# FLIR.net
KiCad netlist of a schematic drawn in Altium Designer
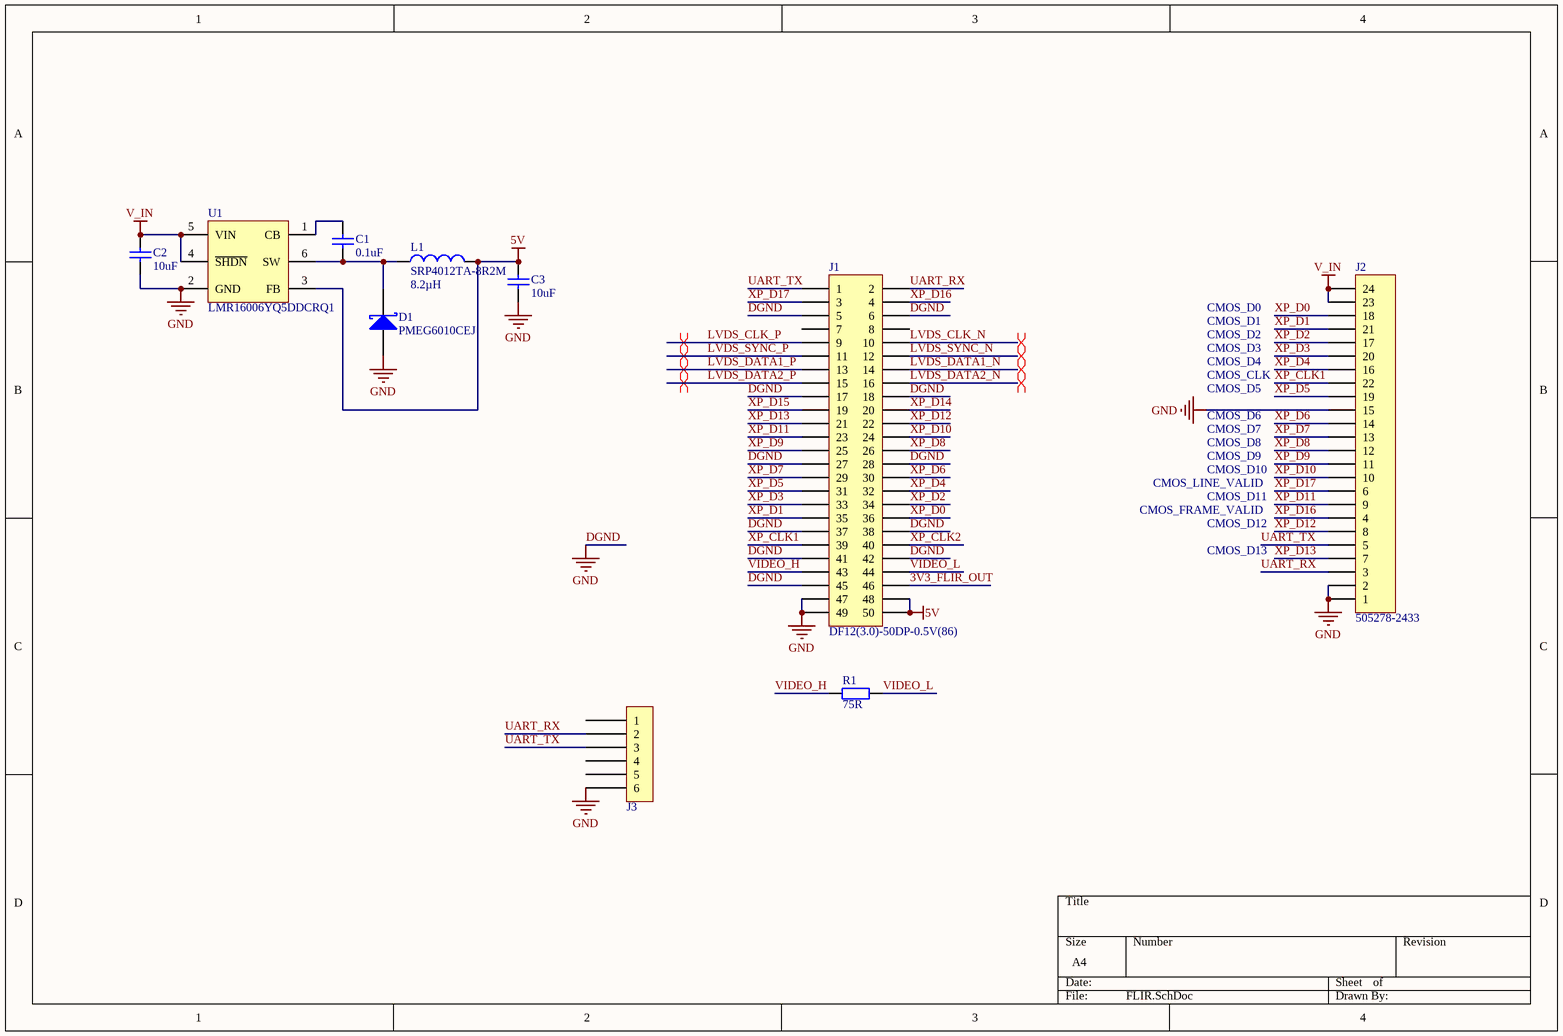
[diagram p0: FLIR.SchDoc]

(export (version "E")
  (design (tool "Eeschema 10.0.6"))
  (components
    (comp (ref "C1")
      (value "0.1uF")
      (footprint "0603C_L")
      (description "CAP CER 0603 0.1uF 16V X7R 5%")
      (fields
        (field (name "MANUFACTURER") "Vishay / Vitramon")
        (field (name "MANUFACTURER PART NUMBER") "VJ0603Y104JXJPW1BC")
      )
      (libsource (lib "KMTI-main") (part "VJ0603Y104JXJPW1BC"))
    )
    (comp (ref "C2")
      (value "10uF")
      (footprint "1206_1.6_L")
      (description "CAP CER 1206 10uF 50V X5R 20%")
      (fields
        (field (name "MANUFACTURER") "Murata Electronics")
        (field (name "MANUFACTURER PART NUMBER") "GRM31CR61H106MA12L")
      )
      (libsource (lib "KMTI-main") (part "GRM31CR61H106MA12L"))
    )
    (comp (ref "C3")
      (value "10uF")
      (footprint "1206_1.6_L")
      (description "CAP CER 1206 10uF 25V X7R 10%")
      (fields
        (field (name "MANUFACTURER") "Taiyo Yuden")
        (field (name "MANUFACTURER PART NUMBER") "TMK316B7106KL-TD")
      )
      (libsource (lib "KMTI-main") (part "TMK316B7106KL-TD"))
    )
    (comp (ref "D1")
      (value "PMEG6010CEJ")
      (footprint "SOD323M")
      (description "DIODE SCHOTTKY 60V 1A SOD323F")
      (fields
        (field (name "MANUFACTURER") "NXP USA Inc.")
        (field (name "MANUFACTURER PART NUMBER") "PMEG6010CEJ,115")
      )
      (libsource (lib "KMTI-main") (part "PMEG6010CEJ,115"))
    )
    (comp (ref "J1")
      (value "DF12(3.0)-50DP-0.5V(86)")
      (footprint "DF12(3.0)-50DP-0.5V(86)")
      (description "Board to Board & Mezzanine Connectors 50P V SMT DR HDR 3.0MM STACK HT GOLD")
      (fields (field (name "MANUFACTURER") "Hirose Connector"))
      (libsource (lib "KMTI-main") (part "DF12(3.0)-50DP-0.5V(86)"))
    )
    (comp (ref "J2")
      (value "505278-2433")
      (footprint "505278-2433")
      (description "0.5 FFC ZIF BTM CONT EMBT PKG 24")
      (fields
        (field (name "MANUFACTURER") "Molex, LLC")
        (field (name "MANUFACTURER PART NUMBER") "5052782433")
      )
      (libsource (lib "KMTI-main") (part "5052782433"))
    )
    (comp (ref "J3")
      (value "BM06B-GHS-TBT(LF)(SN)(N)")
      (footprint "BM06B-GHS-TBT")
      (description "CONN HEADER GH TOP 6POS 1.25MM")
      (fields (field (name "MANUFACTURER") "JST Sales America Inc."))
      (libsource (lib "KMTI-main") (part "BM06B-GHS-TBT(LF)(SN)(N)"))
    )
    (comp (ref "L1")
      (value "SRP4012TA-8R2M")
      (footprint "INDP4541X12M")
      (description "FIXED IND 8.2UH 1.4A 376 MOHM")
      (fields
        (field (name "MANUFACTURER") "Bourns Inc.")
        (field (name "TOLERANCE") "±20%")
        (field (name "INDUCTANCE") "8.2µH")
      )
      (libsource (lib "KMTI-main") (part "SRP4012TA-8R2M"))
    )
    (comp (ref "R1")
      (value "75R")
      (footprint "0603R_0.45_H")
      (description "RES SMD 75 OHM 1% 1/10W 0603")
      (fields
        (field (name "MANUFACTURER") "Vishay Dale")
        (field (name "MANUFACTURER PART NUMBER") "CRCW060375R0FKEA")
      )
      (libsource (lib "KMTI-main") (part "CRCW060375R0FKEA"))
    )
    (comp (ref "U1")
      (value "LMR16006YQ5DDCRQ1")
      (footprint "SOT95P280X110-6M")
      (description "IC REG BUCK 5V 0.6A 6SOT")
      (fields (field (name "MANUFACTURER") "Texas Instruments"))
      (libsource (lib "Power") (part "LMR16006YQ5DDCRQ1"))
    )
  )
  (nets
    (net (code "1") (name "/3V3_FLIR_OUT") (class "Default")
      (node (ref "J1") (pin "46") (pinfunction "46_46") (pintype "passive"))
    )
    (net (code "2") (name "/LVDS_CLK_N") (class "Default")
      (node (ref "J1") (pin "10") (pinfunction "10_10") (pintype "passive"))
    )
    (net (code "3") (name "/LVDS_CLK_P") (class "Default")
      (node (ref "J1") (pin "9") (pinfunction "9_9") (pintype "passive"))
    )
    (net (code "4") (name "/LVDS_DATA1_N") (class "Default")
      (node (ref "J1") (pin "14") (pinfunction "14_14") (pintype "passive"))
    )
    (net (code "5") (name "/LVDS_DATA1_P") (class "Default")
      (node (ref "J1") (pin "13") (pinfunction "13_13") (pintype "passive"))
    )
    (net (code "6") (name "/LVDS_DATA2_N") (class "Default")
      (node (ref "J1") (pin "16") (pinfunction "16_16") (pintype "passive"))
    )
    (net (code "7") (name "/LVDS_DATA2_P") (class "Default")
      (node (ref "J1") (pin "15") (pinfunction "15_15") (pintype "passive"))
    )
    (net (code "8") (name "/LVDS_SYNC_N") (class "Default")
      (node (ref "J1") (pin "12") (pinfunction "12_12") (pintype "passive"))
    )
    (net (code "9") (name "/LVDS_SYNC_P") (class "Default")
      (node (ref "J1") (pin "11") (pinfunction "11_11") (pintype "passive"))
    )
    (net (code "10") (name "/UART_RX") (class "Default")
      (node (ref "J1") (pin "2") (pinfunction "2_2") (pintype "passive"))
      (node (ref "J2") (pin "3") (pinfunction "3_3") (pintype "passive"))
      (node (ref "J3") (pin "2") (pinfunction "2_2") (pintype "passive"))
    )
    (net (code "11") (name "/UART_TX") (class "Default")
      (node (ref "J1") (pin "1") (pinfunction "1_1") (pintype "passive"))
      (node (ref "J2") (pin "5") (pinfunction "5_5") (pintype "passive"))
      (node (ref "J3") (pin "3") (pinfunction "3_3") (pintype "passive"))
    )
    (net (code "12") (name "/VIDEO_H") (class "Default")
      (node (ref "J1") (pin "43") (pinfunction "43_43") (pintype "passive"))
      (node (ref "R1") (pin "1") (pinfunction "1_1") (pintype "passive"))
    )
    (net (code "13") (name "/VIDEO_L") (class "Default")
      (node (ref "J1") (pin "44") (pinfunction "44_44") (pintype "passive"))
      (node (ref "R1") (pin "2") (pinfunction "2_2") (pintype "passive"))
    )
    (net (code "14") (name "/XP_CLK1") (class "Default")
      (node (ref "J1") (pin "39") (pinfunction "39_39") (pintype "passive"))
      (node (ref "J2") (pin "22") (pinfunction "22_22") (pintype "passive"))
    )
    (net (code "15") (name "/XP_CLK2") (class "Default")
      (node (ref "J1") (pin "40") (pinfunction "40_40") (pintype "passive"))
    )
    (net (code "16") (name "/XP_D0") (class "Default")
      (node (ref "J1") (pin "36") (pinfunction "36_36") (pintype "passive"))
      (node (ref "J2") (pin "18") (pinfunction "18_18") (pintype "passive"))
    )
    (net (code "17") (name "/XP_D1") (class "Default")
      (node (ref "J1") (pin "35") (pinfunction "35_35") (pintype "passive"))
      (node (ref "J2") (pin "21") (pinfunction "21_21") (pintype "passive"))
    )
    (net (code "18") (name "/XP_D2") (class "Default")
      (node (ref "J1") (pin "34") (pinfunction "34_34") (pintype "passive"))
      (node (ref "J2") (pin "17") (pinfunction "17_17") (pintype "passive"))
    )
    (net (code "19") (name "/XP_D3") (class "Default")
      (node (ref "J1") (pin "33") (pinfunction "33_33") (pintype "passive"))
      (node (ref "J2") (pin "20") (pinfunction "20_20") (pintype "passive"))
    )
    (net (code "20") (name "/XP_D4") (class "Default")
      (node (ref "J1") (pin "32") (pinfunction "32_32") (pintype "passive"))
      (node (ref "J2") (pin "16") (pinfunction "16_16") (pintype "passive"))
    )
    (net (code "21") (name "/XP_D5") (class "Default")
      (node (ref "J1") (pin "31") (pinfunction "31_31") (pintype "passive"))
      (node (ref "J2") (pin "19") (pinfunction "19_19") (pintype "passive"))
    )
    (net (code "22") (name "/XP_D6") (class "Default")
      (node (ref "J1") (pin "30") (pinfunction "30_30") (pintype "passive"))
      (node (ref "J2") (pin "14") (pinfunction "14_14") (pintype "passive"))
    )
    (net (code "23") (name "/XP_D7") (class "Default")
      (node (ref "J1") (pin "29") (pinfunction "29_29") (pintype "passive"))
      (node (ref "J2") (pin "13") (pinfunction "13_13") (pintype "passive"))
    )
    (net (code "24") (name "/XP_D8") (class "Default")
      (node (ref "J1") (pin "26") (pinfunction "26_26") (pintype "passive"))
      (node (ref "J2") (pin "12") (pinfunction "12_12") (pintype "passive"))
    )
    (net (code "25") (name "/XP_D9") (class "Default")
      (node (ref "J1") (pin "25") (pinfunction "25_25") (pintype "passive"))
      (node (ref "J2") (pin "11") (pinfunction "11_11") (pintype "passive"))
    )
    (net (code "26") (name "/XP_D10") (class "Default")
      (node (ref "J1") (pin "24") (pinfunction "24_24") (pintype "passive"))
      (node (ref "J2") (pin "10") (pinfunction "10_10") (pintype "passive"))
    )
    (net (code "27") (name "/XP_D11") (class "Default")
      (node (ref "J1") (pin "23") (pinfunction "23_23") (pintype "passive"))
      (node (ref "J2") (pin "9") (pinfunction "9_9") (pintype "passive"))
    )
    (net (code "28") (name "/XP_D12") (class "Default")
      (node (ref "J1") (pin "22") (pinfunction "22_22") (pintype "passive"))
      (node (ref "J2") (pin "8") (pinfunction "8_8") (pintype "passive"))
    )
    (net (code "29") (name "/XP_D13") (class "Default")
      (node (ref "J1") (pin "21") (pinfunction "21_21") (pintype "passive"))
      (node (ref "J2") (pin "7") (pinfunction "7_7") (pintype "passive"))
    )
    (net (code "30") (name "/XP_D14") (class "Default")
      (node (ref "J1") (pin "20") (pinfunction "20_20") (pintype "passive"))
    )
    (net (code "31") (name "/XP_D15") (class "Default")
      (node (ref "J1") (pin "19") (pinfunction "19_19") (pintype "passive"))
    )
    (net (code "32") (name "/XP_D16") (class "Default")
      (node (ref "J1") (pin "4") (pinfunction "4_4") (pintype "passive"))
      (node (ref "J2") (pin "4") (pinfunction "4_4") (pintype "passive"))
    )
    (net (code "33") (name "/XP_D17") (class "Default")
      (node (ref "J1") (pin "3") (pinfunction "3_3") (pintype "passive"))
      (node (ref "J2") (pin "6") (pinfunction "6_6") (pintype "passive"))
    )
    (net (code "34") (name "5V") (class "Default")
      (node (ref "C3") (pin "2") (pinfunction "2_2") (pintype "passive"))
      (node (ref "J1") (pin "48") (pinfunction "48_48") (pintype "passive"))
      (node (ref "J1") (pin "50") (pinfunction "50_50") (pintype "passive"))
      (node (ref "L1") (pin "2") (pinfunction "2_2") (pintype "passive"))
      (node (ref "U1") (pin "3") (pinfunction "FB_3") (pintype "passive"))
    )
    (net (code "35") (name "GND") (class "Default")
      (node (ref "C2") (pin "1") (pinfunction "1_1") (pintype "passive"))
      (node (ref "C3") (pin "1") (pinfunction "1_1") (pintype "passive"))
      (node (ref "D1") (pin "2") (pinfunction "A_2") (pintype "passive"))
      (node (ref "J1") (pin "17") (pinfunction "17_17") (pintype "passive"))
      (node (ref "J1") (pin "18") (pinfunction "18_18") (pintype "passive"))
      (node (ref "J1") (pin "27") (pinfunction "27_27") (pintype "passive"))
      (node (ref "J1") (pin "28") (pinfunction "28_28") (pintype "passive"))
      (node (ref "J1") (pin "37") (pinfunction "37_37") (pintype "passive"))
      (node (ref "J1") (pin "38") (pinfunction "38_38") (pintype "passive"))
      (node (ref "J1") (pin "41") (pinfunction "41_41") (pintype "passive"))
      (node (ref "J1") (pin "42") (pinfunction "42_42") (pintype "passive"))
      (node (ref "J1") (pin "45") (pinfunction "45_45") (pintype "passive"))
      (node (ref "J1") (pin "47") (pinfunction "47_47") (pintype "passive"))
      (node (ref "J1") (pin "49") (pinfunction "49_49") (pintype "passive"))
      (node (ref "J1") (pin "5") (pinfunction "5_5") (pintype "passive"))
      (node (ref "J1") (pin "6") (pinfunction "6_6") (pintype "passive"))
      (node (ref "J2") (pin "1") (pinfunction "1_1") (pintype "passive"))
      (node (ref "J2") (pin "15") (pinfunction "15_15") (pintype "passive"))
      (node (ref "J2") (pin "2") (pinfunction "2_2") (pintype "passive"))
      (node (ref "J3") (pin "6") (pinfunction "6_6") (pintype "passive"))
      (node (ref "U1") (pin "2") (pinfunction "GND_2") (pintype "passive"))
    )
    (net (code "36") (name "Net-(D1-K)") (class "Default")
      (node (ref "C1") (pin "1") (pinfunction "1_1") (pintype "passive"))
      (node (ref "D1") (pin "1") (pinfunction "K_1") (pintype "passive"))
      (node (ref "L1") (pin "1") (pinfunction "1_1") (pintype "passive"))
      (node (ref "U1") (pin "6") (pinfunction "SW_6") (pintype "passive"))
    )
    (net (code "37") (name "Net-(U1-CB)") (class "Default")
      (node (ref "C1") (pin "2") (pinfunction "2_2") (pintype "passive"))
      (node (ref "U1") (pin "1") (pinfunction "CB_1") (pintype "passive"))
    )
    (net (code "38") (name "V_IN") (class "Default")
      (node (ref "C2") (pin "2") (pinfunction "2_2") (pintype "passive"))
      (node (ref "J2") (pin "23") (pinfunction "23_23") (pintype "passive"))
      (node (ref "J2") (pin "24") (pinfunction "24_24") (pintype "passive"))
      (node (ref "U1") (pin "4") (pinfunction "~{SHDN}_4") (pintype "passive"))
      (node (ref "U1") (pin "5") (pinfunction "VIN_5") (pintype "passive"))
    )
    (net (code "39") (name "unconnected-(J1-Pad7)") (class "Default")
      (node (ref "J1") (pin "7") (pinfunction "7_7") (pintype "passive"))
    )
    (net (code "40") (name "unconnected-(J1-Pad8)") (class "Default")
      (node (ref "J1") (pin "8") (pinfunction "8_8") (pintype "passive"))
    )
    (net (code "41") (name "unconnected-(J3-Pad1)") (class "Default")
      (node (ref "J3") (pin "1") (pinfunction "1_1") (pintype "passive"))
    )
    (net (code "42") (name "unconnected-(J3-Pad4)") (class "Default")
      (node (ref "J3") (pin "4") (pinfunction "4_4") (pintype "passive"))
    )
    (net (code "43") (name "unconnected-(J3-Pad5)") (class "Default")
      (node (ref "J3") (pin "5") (pinfunction "5_5") (pintype "passive"))
    )
  )
)
